# CondizionamentoTL081.net
KiCad netlist of a schematic drawn in EAGLE
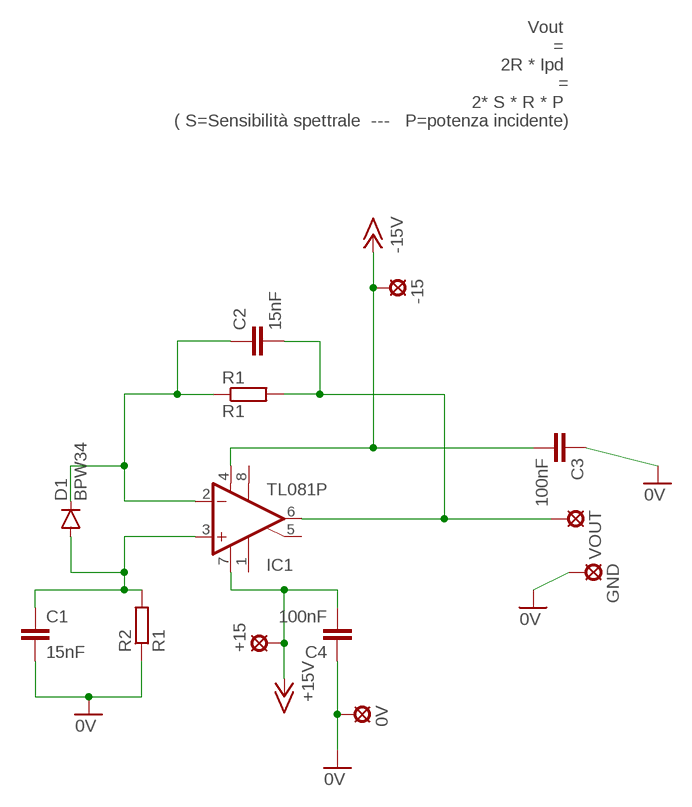
[diagram p0: schematic, sheet 1]

(export (version "E")
  (design (tool "Eeschema 10.0.6"))
  (components
    (comp (ref "+15")
      (value "+15")
      (footprint "eagle-import:LSP10")
      (libsource (lib "eagle-import") (part "LSP10"))
    )
    (comp (ref "-15")
      (value "-15")
      (footprint "eagle-import:LSP10")
      (libsource (lib "eagle-import") (part "LSP10"))
    )
    (comp (ref "0V")
      (value "0V")
      (footprint "eagle-import:LSP10")
      (libsource (lib "eagle-import") (part "LSP10"))
    )
    (comp (ref "C1")
      (value "15nF")
      (footprint "eagle-import:C050-024X044")
      (libsource (lib "eagle-import") (part "C-EU050-024X044"))
    )
    (comp (ref "C2")
      (value "15nF")
      (footprint "eagle-import:C050-024X044")
      (libsource (lib "eagle-import") (part "C-EU050-024X044"))
    )
    (comp (ref "C3")
      (value "100nF")
      (footprint "eagle-import:C050-024X044")
      (libsource (lib "eagle-import") (part "C-EU050-024X044"))
    )
    (comp (ref "C4")
      (value "100nF")
      (footprint "eagle-import:C050-024X044")
      (libsource (lib "eagle-import") (part "C-EU050-024X044"))
    )
    (comp (ref "D1")
      (value "BPW34")
      (footprint "eagle-import:BPW34")
      (libsource (lib "eagle-import") (part "BPW34"))
    )
    (comp (ref "GND")
      (value "0V")
      (footprint "eagle-import:LSP10")
      (libsource (lib "eagle-import") (part "LSP10"))
    )
    (comp (ref "IC1")
      (value "TL081P")
      (footprint "eagle-import:DIL08")
      (libsource (lib "eagle-import") (part "TL081P"))
    )
    (comp (ref "R1")
      (value "R1")
      (footprint "eagle-import:0207_10")
      (libsource (lib "eagle-import") (part "R-EU_0207/10"))
    )
    (comp (ref "R2")
      (value "R1")
      (footprint "eagle-import:0207_10")
      (libsource (lib "eagle-import") (part "R-EU_0207/10"))
    )
    (comp (ref "VOUT")
      (value "Vout")
      (footprint "eagle-import:LSP10")
      (libsource (lib "eagle-import") (part "LSP10"))
    )
  )
  (nets
    (net (code "1") (name "+15V") (class "Default")
      (node (ref "+15") (pin "MP") (pinfunction "MP_MP") (pintype "passive"))
      (node (ref "C4") (pin "2") (pinfunction "2_2") (pintype "passive"))
      (node (ref "IC1") (pin "7") (pinfunction "V+_7") (pintype "power_in"))
    )
    (net (code "2") (name "-15V") (class "Default")
      (node (ref "-15") (pin "MP") (pinfunction "MP_MP") (pintype "passive"))
      (node (ref "C3") (pin "2") (pinfunction "2_2") (pintype "passive"))
      (node (ref "IC1") (pin "4") (pinfunction "V-_4") (pintype "power_in"))
    )
    (net (code "3") (name "0V") (class "Default")
      (node (ref "0V") (pin "MP") (pinfunction "MP_MP") (pintype "passive"))
      (node (ref "C1") (pin "2") (pinfunction "2_2") (pintype "passive"))
      (node (ref "C3") (pin "1") (pinfunction "1_1") (pintype "passive"))
      (node (ref "C4") (pin "1") (pinfunction "1_1") (pintype "passive"))
      (node (ref "GND") (pin "MP") (pinfunction "MP_MP") (pintype "passive"))
      (node (ref "R2") (pin "1") (pinfunction "1_1") (pintype "passive"))
    )
    (net (code "4") (name "Net-(D1-A)") (class "Default")
      (node (ref "C1") (pin "1") (pinfunction "1_1") (pintype "passive"))
      (node (ref "D1") (pin "P$1") (pinfunction "A_P$1") (pintype "passive"))
      (node (ref "IC1") (pin "3") (pinfunction "+IN_3") (pintype "input"))
      (node (ref "R2") (pin "2") (pinfunction "2_2") (pintype "passive"))
    )
    (net (code "5") (name "Net-(D1-C)") (class "Default")
      (node (ref "C2") (pin "1") (pinfunction "1_1") (pintype "passive"))
      (node (ref "D1") (pin "P$2") (pinfunction "C_P$2") (pintype "passive"))
      (node (ref "IC1") (pin "2") (pinfunction "-IN_2") (pintype "input"))
      (node (ref "R1") (pin "1") (pinfunction "1_1") (pintype "passive"))
    )
    (net (code "6") (name "Net-(IC1-OUT)") (class "Default")
      (node (ref "C2") (pin "2") (pinfunction "2_2") (pintype "passive"))
      (node (ref "IC1") (pin "6") (pinfunction "OUT_6") (pintype "output"))
      (node (ref "R1") (pin "2") (pinfunction "2_2") (pintype "passive"))
      (node (ref "VOUT") (pin "MP") (pinfunction "MP_MP") (pintype "passive"))
    )
    (net (code "7") (name "unconnected-(IC1-ON1-Pad1)") (class "Default")
      (node (ref "IC1") (pin "1") (pinfunction "ON1_1") (pintype "passive"))
    )
    (net (code "8") (name "unconnected-(IC1-ON2-Pad5)") (class "Default")
      (node (ref "IC1") (pin "5") (pinfunction "ON2_5") (pintype "passive"))
    )
    (net (code "9") (name "unconnected-(IC1-OPT-Pad8)") (class "Default")
      (node (ref "IC1") (pin "8") (pinfunction "OPT_8") (pintype "passive"))
    )
  )
)
